# Inverter.net
KiCad netlist of a schematic drawn in EAGLE
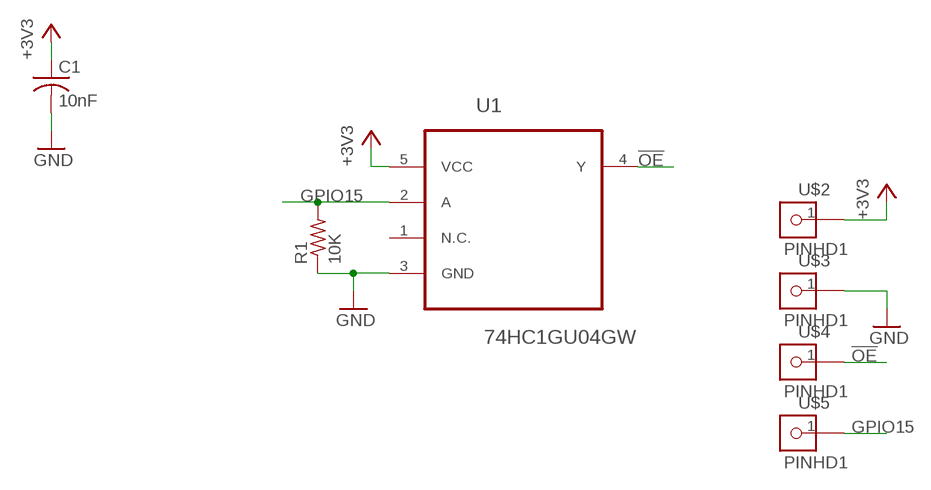
[diagram p0: schematic, sheet 1]

(export (version "E")
  (design (tool "Eeschema 10.0.6"))
  (components
    (comp (ref "C1")
      (value "10nF")
      (footprint "eagle-import:C0805K")
      (libsource (lib "eagle-import") (part "C-USC0805K"))
    )
    (comp (ref "R1")
      (value "10K")
      (footprint "eagle-import:M0805")
      (libsource (lib "eagle-import") (part "R-US_M0805"))
    )
    (comp (ref "U$2")
      (value "PINHD1")
      (footprint "eagle-import:1X1")
      (libsource (lib "eagle-import") (part "PINHD1"))
    )
    (comp (ref "U$3")
      (value "PINHD1")
      (footprint "eagle-import:1X1")
      (libsource (lib "eagle-import") (part "PINHD1"))
    )
    (comp (ref "U$4")
      (value "PINHD1")
      (footprint "eagle-import:1X1")
      (libsource (lib "eagle-import") (part "PINHD1"))
    )
    (comp (ref "U$5")
      (value "PINHD1")
      (footprint "eagle-import:1X1")
      (libsource (lib "eagle-import") (part "PINHD1"))
    )
    (comp (ref "U1")
      (value "74HC1GU04GW")
      (footprint "eagle-import:SOT65P210X110-5N")
      (libsource (lib "eagle-import") (part "74HC1GU04GW"))
    )
  )
  (nets
    (net (code "1") (name "+3V3") (class "Default")
      (node (ref "C1") (pin "1") (pinfunction "1_1") (pintype "passive"))
      (node (ref "U$2") (pin "1") (pinfunction "1_1") (pintype "passive"))
      (node (ref "U1") (pin "5") (pinfunction "VCC_5") (pintype "power_in"))
    )
    (net (code "2") (name "/GPIO15") (class "Default")
      (node (ref "R1") (pin "2") (pinfunction "2_2") (pintype "passive"))
      (node (ref "U$5") (pin "1") (pinfunction "1_1") (pintype "passive"))
      (node (ref "U1") (pin "2") (pinfunction "A_2") (pintype "input"))
    )
    (net (code "3") (name "/~{OE}") (class "Default")
      (node (ref "U$4") (pin "1") (pinfunction "1_1") (pintype "passive"))
      (node (ref "U1") (pin "4") (pinfunction "Y_4") (pintype "output"))
    )
    (net (code "4") (name "GND") (class "Default")
      (node (ref "C1") (pin "2") (pinfunction "2_2") (pintype "passive"))
      (node (ref "R1") (pin "1") (pinfunction "1_1") (pintype "passive"))
      (node (ref "U$3") (pin "1") (pinfunction "1_1") (pintype "passive"))
      (node (ref "U1") (pin "3") (pinfunction "GND_3") (pintype "passive"))
    )
    (net (code "5") (name "unconnected-(U1-N.C.-Pad1)") (class "Default")
      (node (ref "U1") (pin "1") (pinfunction "N.C._1") (pintype "no_connect"))
    )
  )
)
